# Logic.net
KiCad netlist of a schematic drawn in Altium Designer
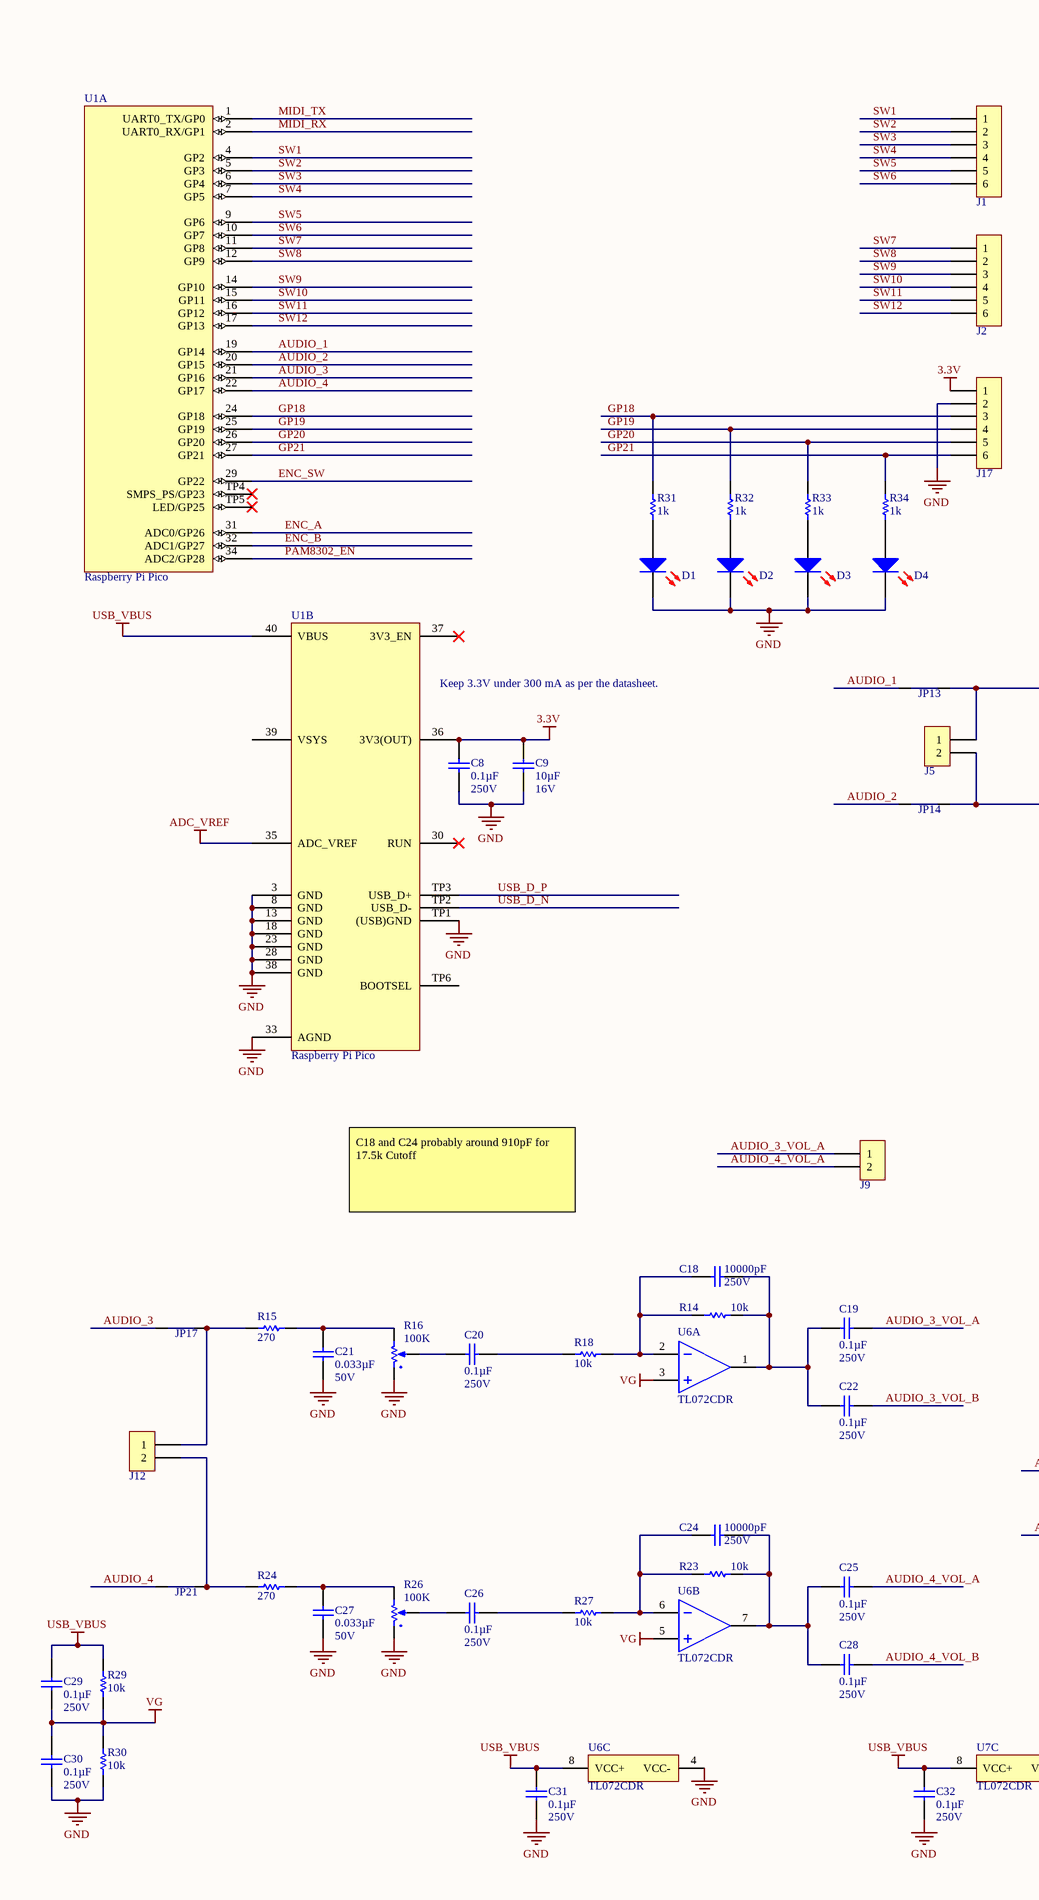
[diagram p0: Logic.SchDoc, left]
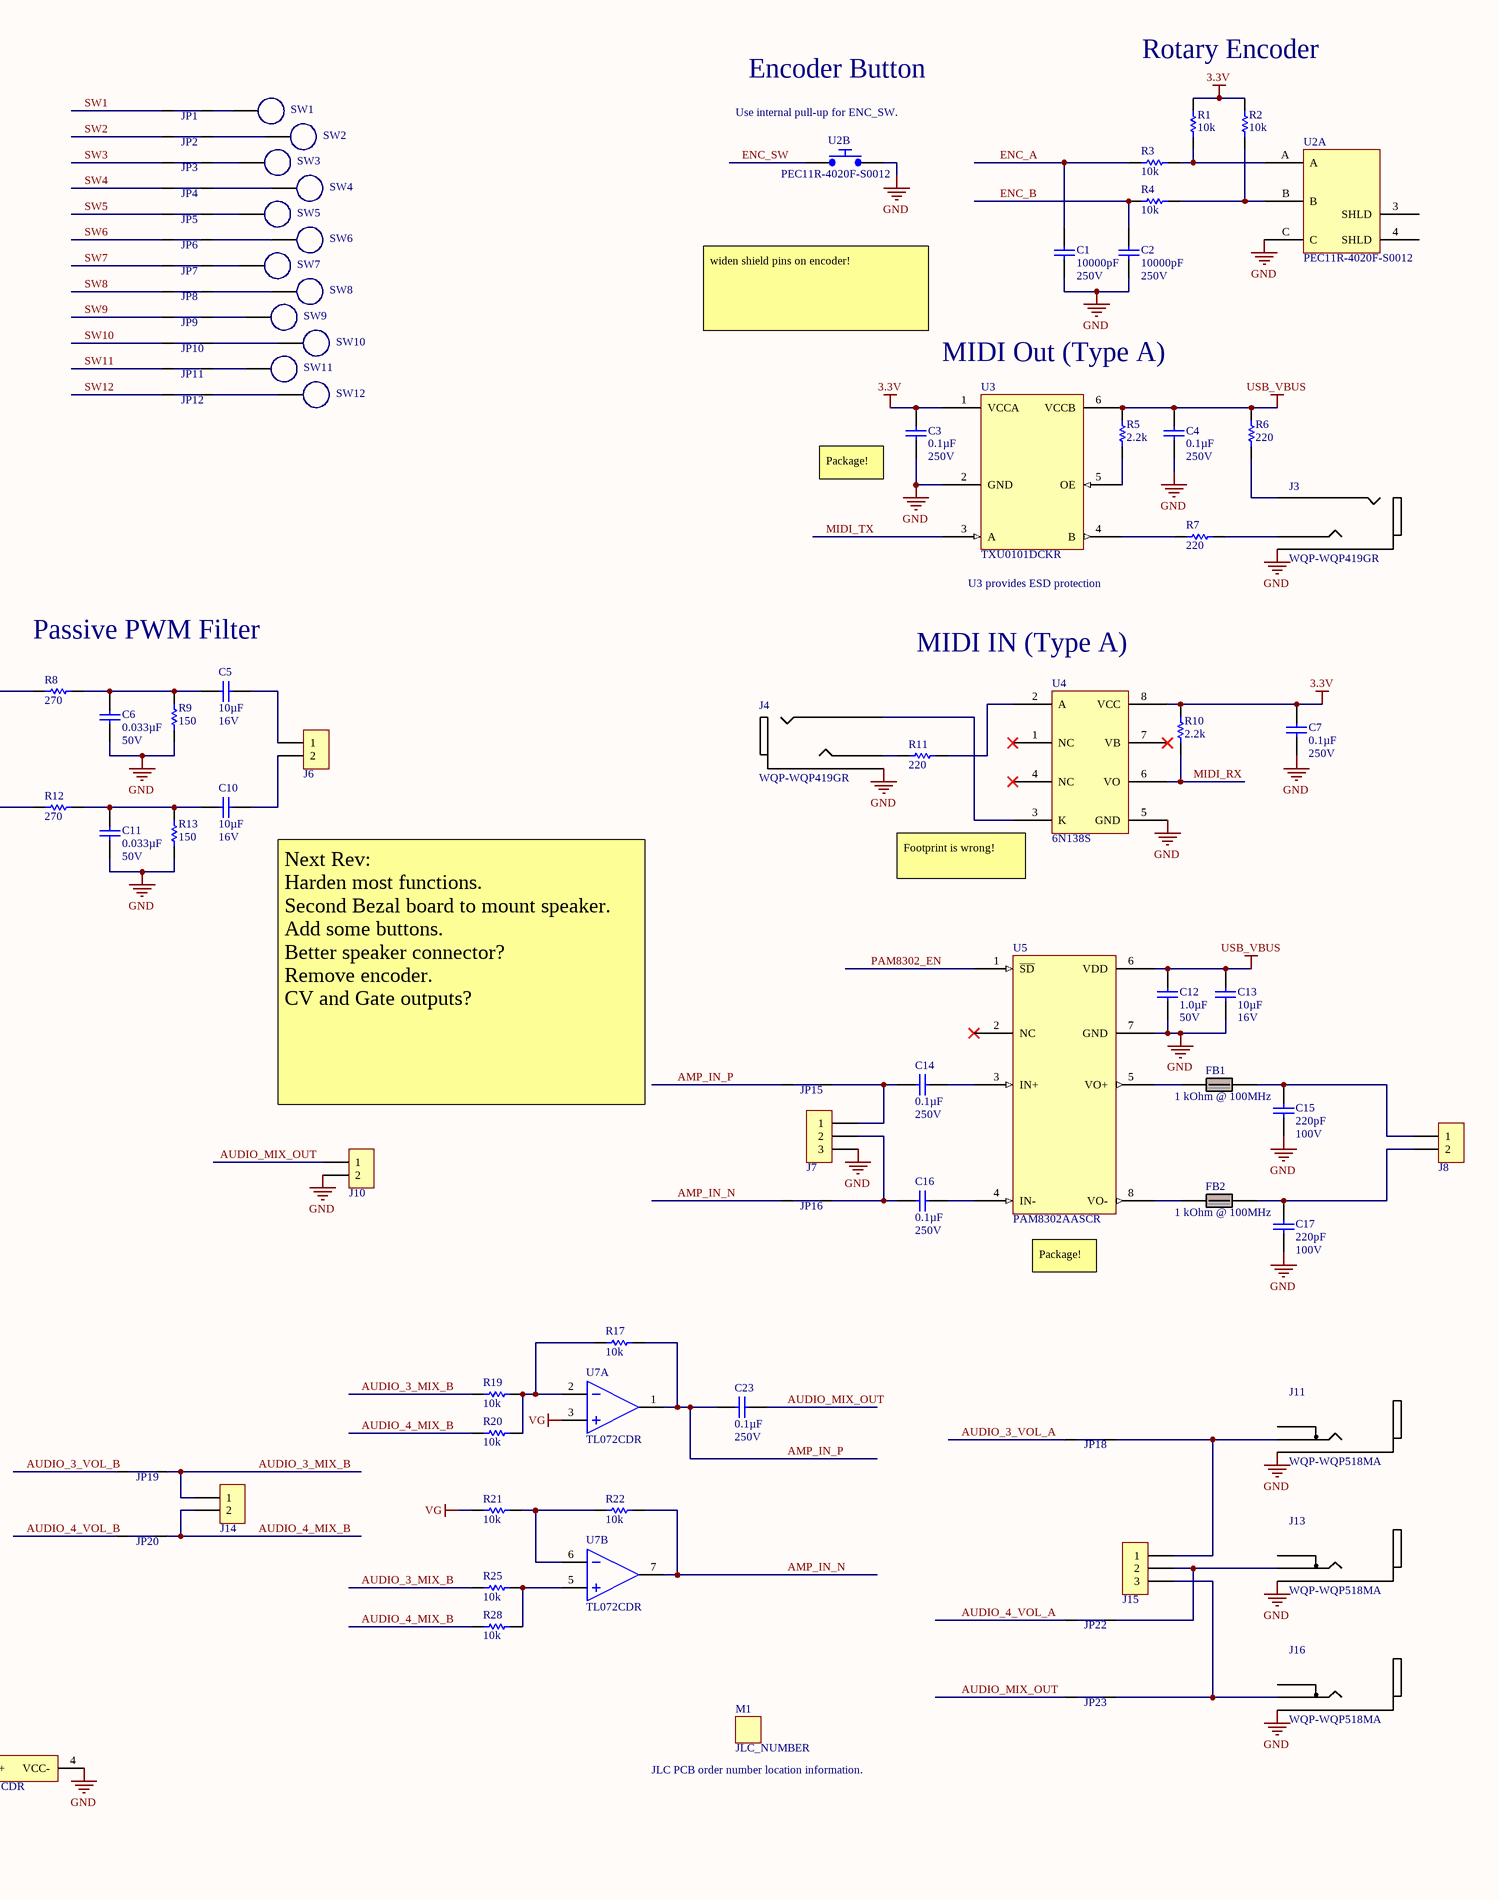
[diagram p1: Logic.SchDoc, right]

(export (version "E")
  (design (tool "Eeschema 10.0.6"))
  (components
    (comp (ref "C1")
      (value "10000pF")
      (footprint "Chip0805")
      (description "CAP CER 10000PF 250V X7R 0805")
      (fields
        (field (name "VOLTAGE") "250V")
        (field (name "PARTNUMBER") "C2012X7R2E103M125AE")
        (field (name "MANUFACTURER") "TDK Corporation")
      )
      (libsource (lib "Passives") (part "CAP"))
    )
    (comp (ref "C2")
      (value "10000pF")
      (footprint "Chip0805")
      (description "CAP CER 10000PF 250V X7R 0805")
      (fields
        (field (name "VOLTAGE") "250V")
        (field (name "PARTNUMBER") "C2012X7R2E103M125AE")
        (field (name "MANUFACTURER") "TDK Corporation")
      )
      (libsource (lib "Passives") (part "CAP"))
    )
    (comp (ref "C3")
      (value "0.1µF")
      (footprint "Chip0805")
      (description "CAP CER 0.1UF 250V 10% X7T 0805")
      (fields
        (field (name "VOLTAGE") "250V")
        (field (name "PARTNUMBER") "C2012X7T2E104K125AA")
        (field (name "MANUFACTURER") "TDK Corporation")
      )
      (libsource (lib "Passives") (part "CAP"))
    )
    (comp (ref "C4")
      (value "0.1µF")
      (footprint "Chip0805")
      (description "CAP CER 0.1UF 250V 10% X7T 0805")
      (fields
        (field (name "VOLTAGE") "250V")
        (field (name "PARTNUMBER") "C2012X7T2E104K125AA")
        (field (name "MANUFACTURER") "TDK Corporation")
      )
      (libsource (lib "Passives") (part "CAP"))
    )
    (comp (ref "C5")
      (value "10µF")
      (footprint "Chip0805")
      (description "CAP CER 10UF 16V 10% X5R 0805")
      (fields
        (field (name "VOLTAGE") "16V")
        (field (name "PARTNUMBER") "C2012X5R1C106K125AC")
        (field (name "MANUFACTURER") "TDK Corporation")
      )
      (libsource (lib "Passives") (part "CAP"))
    )
    (comp (ref "C6")
      (value "0.033µF")
      (footprint "Chip0805")
      (description "CAP CER 0.033UF 50V 5% NP0 0805")
      (fields
        (field (name "VOLTAGE") "50V")
        (field (name "PARTNUMBER") "C2012C0G1H333J125AA")
        (field (name "MANUFACTURER") "TDK Corporation")
      )
      (libsource (lib "Passives") (part "CAP"))
    )
    (comp (ref "C7")
      (value "0.1µF")
      (footprint "Chip0805")
      (description "CAP CER 0.1UF 250V 10% X7T 0805")
      (fields
        (field (name "VOLTAGE") "250V")
        (field (name "PARTNUMBER") "C2012X7T2E104K125AA")
        (field (name "MANUFACTURER") "TDK Corporation")
      )
      (libsource (lib "Passives") (part "CAP"))
    )
    (comp (ref "C8")
      (value "0.1µF")
      (footprint "Chip0805")
      (description "CAP CER 0.1UF 250V 10% X7T 0805")
      (fields
        (field (name "VOLTAGE") "250V")
        (field (name "PARTNUMBER") "C2012X7T2E104K125AA")
        (field (name "MANUFACTURER") "TDK Corporation")
      )
      (libsource (lib "Passives") (part "CAP"))
    )
    (comp (ref "C9")
      (value "10µF")
      (footprint "Chip0805")
      (description "CAP CER 10UF 16V 10% X5R 0805")
      (fields
        (field (name "VOLTAGE") "16V")
        (field (name "PARTNUMBER") "C2012X5R1C106K125AC")
        (field (name "MANUFACTURER") "TDK Corporation")
      )
      (libsource (lib "Passives") (part "CAP"))
    )
    (comp (ref "C10")
      (value "10µF")
      (footprint "Chip0805")
      (description "CAP CER 10UF 16V 10% X5R 0805")
      (fields
        (field (name "VOLTAGE") "16V")
        (field (name "PARTNUMBER") "C2012X5R1C106K125AC")
        (field (name "MANUFACTURER") "TDK Corporation")
      )
      (libsource (lib "Passives") (part "CAP"))
    )
    (comp (ref "C11")
      (value "0.033µF")
      (footprint "Chip0805")
      (description "CAP CER 0.033UF 50V 5% NP0 0805")
      (fields
        (field (name "VOLTAGE") "50V")
        (field (name "PARTNUMBER") "C2012C0G1H333J125AA")
        (field (name "MANUFACTURER") "TDK Corporation")
      )
      (libsource (lib "Passives") (part "CAP"))
    )
    (comp (ref "C12")
      (value "1.0µF")
      (footprint "Chip0805")
      (description "CAP CER 1UF 50V 20% X7R 0805")
      (fields
        (field (name "VOLTAGE") "50V")
        (field (name "PARTNUMBER") "C2012X7R1H105M125AB")
        (field (name "MANUFACTURER") "TDK Corporation")
      )
      (libsource (lib "Passives") (part "CAP"))
    )
    (comp (ref "C13")
      (value "10µF")
      (footprint "Chip0805")
      (description "CAP CER 10UF 16V 10% X5R 0805")
      (fields
        (field (name "VOLTAGE") "16V")
        (field (name "PARTNUMBER") "C2012X5R1C106K125AC")
        (field (name "MANUFACTURER") "TDK Corporation")
      )
      (libsource (lib "Passives") (part "CAP"))
    )
    (comp (ref "C14")
      (value "0.1µF")
      (footprint "Chip0805")
      (description "CAP CER 0.1UF 250V 10% X7T 0805")
      (fields
        (field (name "VOLTAGE") "250V")
        (field (name "PARTNUMBER") "C2012X7T2E104K125AA")
        (field (name "MANUFACTURER") "TDK Corporation")
      )
      (libsource (lib "Passives") (part "CAP"))
    )
    (comp (ref "C15")
      (value "220pF")
      (footprint "Chip0805")
      (description "CAP CER 220PF 100V 5% NP0 0805")
      (fields
        (field (name "VOLTAGE") "100V")
        (field (name "PARTNUMBER") "C2012C0G2A221J")
        (field (name "MANUFACTURER") "TDK Corporation")
      )
      (libsource (lib "Passives") (part "CAP"))
    )
    (comp (ref "C16")
      (value "0.1µF")
      (footprint "Chip0805")
      (description "CAP CER 0.1UF 250V 10% X7T 0805")
      (fields
        (field (name "VOLTAGE") "250V")
        (field (name "PARTNUMBER") "C2012X7T2E104K125AA")
        (field (name "MANUFACTURER") "TDK Corporation")
      )
      (libsource (lib "Passives") (part "CAP"))
    )
    (comp (ref "C17")
      (value "220pF")
      (footprint "Chip0805")
      (description "CAP CER 220PF 100V 5% NP0 0805")
      (fields
        (field (name "VOLTAGE") "100V")
        (field (name "PARTNUMBER") "C2012C0G2A221J")
        (field (name "MANUFACTURER") "TDK Corporation")
      )
      (libsource (lib "Passives") (part "CAP"))
    )
    (comp (ref "C18")
      (value "10000pF")
      (footprint "Chip0805")
      (description "CAP CER 10000PF 250V X7R 0805")
      (fields
        (field (name "VOLTAGE") "250V")
        (field (name "PARTNUMBER") "C2012X7R2E103M125AE")
        (field (name "MANUFACTURER") "TDK Corporation")
      )
      (libsource (lib "Passives") (part "CAP"))
    )
    (comp (ref "C19")
      (value "0.1µF")
      (footprint "Chip0805")
      (description "CAP CER 0.1UF 250V 10% X7T 0805")
      (fields
        (field (name "VOLTAGE") "250V")
        (field (name "PARTNUMBER") "C2012X7T2E104K125AA")
        (field (name "MANUFACTURER") "TDK Corporation")
      )
      (libsource (lib "Passives") (part "CAP"))
    )
    (comp (ref "C20")
      (value "0.1µF")
      (footprint "Chip0805")
      (description "CAP CER 0.1UF 250V 10% X7T 0805")
      (fields
        (field (name "VOLTAGE") "250V")
        (field (name "PARTNUMBER") "C2012X7T2E104K125AA")
        (field (name "MANUFACTURER") "TDK Corporation")
      )
      (libsource (lib "Passives") (part "CAP"))
    )
    (comp (ref "C21")
      (value "0.033µF")
      (footprint "Chip0805")
      (description "CAP CER 0.033UF 50V 5% NP0 0805")
      (fields
        (field (name "VOLTAGE") "50V")
        (field (name "PARTNUMBER") "C2012C0G1H333J125AA")
        (field (name "MANUFACTURER") "TDK Corporation")
      )
      (libsource (lib "Passives") (part "CAP"))
    )
    (comp (ref "C22")
      (value "0.1µF")
      (footprint "Chip0805")
      (description "CAP CER 0.1UF 250V 10% X7T 0805")
      (fields
        (field (name "VOLTAGE") "250V")
        (field (name "PARTNUMBER") "C2012X7T2E104K125AA")
        (field (name "MANUFACTURER") "TDK Corporation")
      )
      (libsource (lib "Passives") (part "CAP"))
    )
    (comp (ref "C23")
      (value "0.1µF")
      (footprint "Chip0805")
      (description "CAP CER 0.1UF 250V 10% X7T 0805")
      (fields
        (field (name "VOLTAGE") "250V")
        (field (name "PARTNUMBER") "C2012X7T2E104K125AA")
        (field (name "MANUFACTURER") "TDK Corporation")
      )
      (libsource (lib "Passives") (part "CAP"))
    )
    (comp (ref "C24")
      (value "10000pF")
      (footprint "Chip0805")
      (description "CAP CER 10000PF 250V X7R 0805")
      (fields
        (field (name "VOLTAGE") "250V")
        (field (name "PARTNUMBER") "C2012X7R2E103M125AE")
        (field (name "MANUFACTURER") "TDK Corporation")
      )
      (libsource (lib "Passives") (part "CAP"))
    )
    (comp (ref "C25")
      (value "0.1µF")
      (footprint "Chip0805")
      (description "CAP CER 0.1UF 250V 10% X7T 0805")
      (fields
        (field (name "VOLTAGE") "250V")
        (field (name "PARTNUMBER") "C2012X7T2E104K125AA")
        (field (name "MANUFACTURER") "TDK Corporation")
      )
      (libsource (lib "Passives") (part "CAP"))
    )
    (comp (ref "C26")
      (value "0.1µF")
      (footprint "Chip0805")
      (description "CAP CER 0.1UF 250V 10% X7T 0805")
      (fields
        (field (name "VOLTAGE") "250V")
        (field (name "PARTNUMBER") "C2012X7T2E104K125AA")
        (field (name "MANUFACTURER") "TDK Corporation")
      )
      (libsource (lib "Passives") (part "CAP"))
    )
    (comp (ref "C27")
      (value "0.033µF")
      (footprint "Chip0805")
      (description "CAP CER 0.033UF 50V 5% NP0 0805")
      (fields
        (field (name "VOLTAGE") "50V")
        (field (name "PARTNUMBER") "C2012C0G1H333J125AA")
        (field (name "MANUFACTURER") "TDK Corporation")
      )
      (libsource (lib "Passives") (part "CAP"))
    )
    (comp (ref "C28")
      (value "0.1µF")
      (footprint "Chip0805")
      (description "CAP CER 0.1UF 250V 10% X7T 0805")
      (fields
        (field (name "VOLTAGE") "250V")
        (field (name "PARTNUMBER") "C2012X7T2E104K125AA")
        (field (name "MANUFACTURER") "TDK Corporation")
      )
      (libsource (lib "Passives") (part "CAP"))
    )
    (comp (ref "C29")
      (value "0.1µF")
      (footprint "Chip0805")
      (description "CAP CER 0.1UF 250V 10% X7T 0805")
      (fields
        (field (name "VOLTAGE") "250V")
        (field (name "PARTNUMBER") "C2012X7T2E104K125AA")
        (field (name "MANUFACTURER") "TDK Corporation")
      )
      (libsource (lib "Passives") (part "CAP"))
    )
    (comp (ref "C30")
      (value "0.1µF")
      (footprint "Chip0805")
      (description "CAP CER 0.1UF 250V 10% X7T 0805")
      (fields
        (field (name "VOLTAGE") "250V")
        (field (name "PARTNUMBER") "C2012X7T2E104K125AA")
        (field (name "MANUFACTURER") "TDK Corporation")
      )
      (libsource (lib "Passives") (part "CAP"))
    )
    (comp (ref "C31")
      (value "0.1µF")
      (footprint "Chip0805")
      (description "CAP CER 0.1UF 250V 10% X7T 0805")
      (fields
        (field (name "VOLTAGE") "250V")
        (field (name "PARTNUMBER") "C2012X7T2E104K125AA")
        (field (name "MANUFACTURER") "TDK Corporation")
      )
      (libsource (lib "Passives") (part "CAP"))
    )
    (comp (ref "C32")
      (value "0.1µF")
      (footprint "Chip0805")
      (description "CAP CER 0.1UF 250V 10% X7T 0805")
      (fields
        (field (name "VOLTAGE") "250V")
        (field (name "PARTNUMBER") "C2012X7T2E104K125AA")
        (field (name "MANUFACTURER") "TDK Corporation")
      )
      (libsource (lib "Passives") (part "CAP"))
    )
    (comp (ref "D1")
      (value "RED")
      (footprint "LED0603")
      (description "LED SUPER RED CLR THIN 0603 SMD")
      (fields (field (name "PARTNUMBER") "LTST-C191KRKT") (field (name "MANUFACTURER") "Lite-On Inc"))
      (libsource (lib "Optoelectronics") (part "LED_RED"))
    )
    (comp (ref "D2")
      (value "RED")
      (footprint "LED0603")
      (description "LED SUPER RED CLR THIN 0603 SMD")
      (fields (field (name "PARTNUMBER") "LTST-C191KRKT") (field (name "MANUFACTURER") "Lite-On Inc"))
      (libsource (lib "Optoelectronics") (part "LED_RED"))
    )
    (comp (ref "D3")
      (value "RED")
      (footprint "LED0603")
      (description "LED SUPER RED CLR THIN 0603 SMD")
      (fields (field (name "PARTNUMBER") "LTST-C191KRKT") (field (name "MANUFACTURER") "Lite-On Inc"))
      (libsource (lib "Optoelectronics") (part "LED_RED"))
    )
    (comp (ref "D4")
      (value "RED")
      (footprint "LED0603")
      (description "LED SUPER RED CLR THIN 0603 SMD")
      (fields (field (name "PARTNUMBER") "LTST-C191KRKT") (field (name "MANUFACTURER") "Lite-On Inc"))
      (libsource (lib "Optoelectronics") (part "LED_RED"))
    )
    (comp (ref "FB1")
      (value "FERRITE")
      (footprint "Chip0805")
      (description "FERRITE BEAD 1000 OHM .20A 0805")
      (fields
        (field (name "IMPEDANCE @ FREQUENCY") "1 kOhm @ 100MHz")
        (field (name "PARTNUMBER") "74279205")
        (field (name "MANUFACTURER") "Wurth Electronics Inc")
      )
      (libsource (lib "Passives") (part "FERRITE"))
    )
    (comp (ref "FB2")
      (value "FERRITE")
      (footprint "Chip0805")
      (description "FERRITE BEAD 1000 OHM .20A 0805")
      (fields
        (field (name "IMPEDANCE @ FREQUENCY") "1 kOhm @ 100MHz")
        (field (name "PARTNUMBER") "74279205")
        (field (name "MANUFACTURER") "Wurth Electronics Inc")
      )
      (libsource (lib "Passives") (part "FERRITE"))
    )
    (comp (ref "J1")
      (value "HEADER_1x6_NO_BOM")
      (footprint "HEADER_1x6_100mil_NP")
      (libsource (lib "Mechanical") (part "HEADER_1x6_NO_BOM"))
    )
    (comp (ref "J2")
      (value "HEADER_1x6_NO_BOM")
      (footprint "HEADER_1x6_100mil_NP")
      (libsource (lib "Mechanical") (part "HEADER_1x6_NO_BOM"))
    )
    (comp (ref "J3")
      (value "WQP-WQP419GR")
      (footprint "PJ366ST")
      (description "CONN 3.5mm VIRTICAL STEREO")
      (fields (field (name "MANUFACTURER") "QingPu"))
      (libsource (lib "Connectors") (part "PJ366ST"))
    )
    (comp (ref "J4")
      (value "WQP-WQP419GR")
      (footprint "PJ366ST")
      (description "CONN 3.5mm VIRTICAL STEREO")
      (fields (field (name "MANUFACTURER") "QingPu"))
      (libsource (lib "Connectors") (part "PJ366ST"))
    )
    (comp (ref "J5")
      (value "HEADER_1x2_NO_BOM")
      (footprint "HEADER_1x2_100mil_NP")
      (libsource (lib "") (part "HEADER_1x2_NO_BOM_1"))
    )
    (comp (ref "J6")
      (value "HEADER_1x2_NO_BOM")
      (footprint "HEADER_1x2_100mil_NP")
      (libsource (lib "Mechanical") (part "HEADER_1x2_NO_BOM"))
    )
    (comp (ref "J7")
      (value "HEADER_1x3_NO_BOM")
      (footprint "HEADER_1x3_100mil_NP")
      (libsource (lib "Mechanical") (part "HEADER_1x3_NO_BOM"))
    )
    (comp (ref "J8")
      (value "HEADER_1x2_NO_BOM")
      (footprint "HEADER_1x2_100mil_NP")
      (libsource (lib "Mechanical") (part "HEADER_1x2_NO_BOM"))
    )
    (comp (ref "J9")
      (value "HEADER_1x2_NO_BOM")
      (footprint "HEADER_1x2_100mil_NP")
      (libsource (lib "Mechanical") (part "HEADER_1x2_NO_BOM"))
    )
    (comp (ref "J10")
      (value "HEADER_1x2_NO_BOM")
      (footprint "HEADER_1x2_100mil_NP")
      (libsource (lib "Mechanical") (part "HEADER_1x2_NO_BOM"))
    )
    (comp (ref "J11")
      (value "WQP-WQP518MA")
      (footprint "PJ301M-12")
      (description "CONN 3.5mm VIRTICAL MONO w/ NORMAL")
      (fields (field (name "MANUFACTURER") "QingPu"))
      (libsource (lib "Connectors") (part "PJ301M-12"))
    )
    (comp (ref "J12")
      (value "HEADER_1x2_NO_BOM")
      (footprint "HEADER_1x2_100mil_NP")
      (libsource (lib "") (part "HEADER_1x2_NO_BOM_1"))
    )
    (comp (ref "J13")
      (value "WQP-WQP518MA")
      (footprint "PJ301M-12")
      (description "CONN 3.5mm VIRTICAL MONO w/ NORMAL")
      (fields (field (name "MANUFACTURER") "QingPu"))
      (libsource (lib "Connectors") (part "PJ301M-12"))
    )
    (comp (ref "J14")
      (value "HEADER_1x2_NO_BOM")
      (footprint "HEADER_1x2_100mil_NP")
      (libsource (lib "Mechanical") (part "HEADER_1x2_NO_BOM"))
    )
    (comp (ref "J15")
      (value "HEADER_1x3_NO_BOM")
      (footprint "HEADER_1x3_100mil_NP")
      (libsource (lib "Mechanical") (part "HEADER_1x3_NO_BOM"))
    )
    (comp (ref "J16")
      (value "WQP-WQP518MA")
      (footprint "PJ301M-12")
      (description "CONN 3.5mm VIRTICAL MONO w/ NORMAL")
      (fields (field (name "MANUFACTURER") "QingPu"))
      (libsource (lib "Connectors") (part "PJ301M-12"))
    )
    (comp (ref "J17")
      (value "HEADER_1x6_NO_BOM")
      (footprint "HEADER_1x6_100mil_NP")
      (libsource (lib "Mechanical") (part "HEADER_1x6_NO_BOM"))
    )
    (comp (ref "JP1")
      (value "JUMMPER_NC_0805")
      (footprint "JUMMPER_NC_0805")
      (libsource (lib "Mechanical") (part "JUMPER_NC"))
    )
    (comp (ref "JP2")
      (value "JUMMPER_NC_0805")
      (footprint "JUMMPER_NC_0805")
      (libsource (lib "Mechanical") (part "JUMPER_NC"))
    )
    (comp (ref "JP3")
      (value "JUMMPER_NC_0805")
      (footprint "JUMMPER_NC_0805")
      (libsource (lib "Mechanical") (part "JUMPER_NC"))
    )
    (comp (ref "JP4")
      (value "JUMMPER_NC_0805")
      (footprint "JUMMPER_NC_0805")
      (libsource (lib "Mechanical") (part "JUMPER_NC"))
    )
    (comp (ref "JP5")
      (value "JUMMPER_NC_0805")
      (footprint "JUMMPER_NC_0805")
      (libsource (lib "Mechanical") (part "JUMPER_NC"))
    )
    (comp (ref "JP6")
      (value "JUMMPER_NC_0805")
      (footprint "JUMMPER_NC_0805")
      (libsource (lib "Mechanical") (part "JUMPER_NC"))
    )
    (comp (ref "JP7")
      (value "JUMMPER_NC_0805")
      (footprint "JUMMPER_NC_0805")
      (libsource (lib "Mechanical") (part "JUMPER_NC"))
    )
    (comp (ref "JP8")
      (value "JUMMPER_NC_0805")
      (footprint "JUMMPER_NC_0805")
      (libsource (lib "Mechanical") (part "JUMPER_NC"))
    )
    (comp (ref "JP9")
      (value "JUMMPER_NC_0805")
      (footprint "JUMMPER_NC_0805")
      (libsource (lib "Mechanical") (part "JUMPER_NC"))
    )
    (comp (ref "JP10")
      (value "JUMMPER_NC_0805")
      (footprint "JUMMPER_NC_0805")
      (libsource (lib "Mechanical") (part "JUMPER_NC"))
    )
    (comp (ref "JP11")
      (value "JUMMPER_NC_0805")
      (footprint "JUMMPER_NC_0805")
      (libsource (lib "Mechanical") (part "JUMPER_NC"))
    )
    (comp (ref "JP12")
      (value "JUMMPER_NC_0805")
      (footprint "JUMMPER_NC_0805")
      (libsource (lib "Mechanical") (part "JUMPER_NC"))
    )
    (comp (ref "JP13")
      (value "JUMMPER_NC_0805")
      (footprint "JUMMPER_NC_0805")
      (libsource (lib "Mechanical") (part "JUMPER_NC"))
    )
    (comp (ref "JP14")
      (value "JUMMPER_NC_0805")
      (footprint "JUMMPER_NC_0805")
      (libsource (lib "Mechanical") (part "JUMPER_NC"))
    )
    (comp (ref "JP15")
      (value "JUMMPER_NC_0805")
      (footprint "JUMMPER_NC_0805")
      (libsource (lib "Mechanical") (part "JUMPER_NC"))
    )
    (comp (ref "JP16")
      (value "JUMMPER_NC_0805")
      (footprint "JUMMPER_NC_0805")
      (libsource (lib "Mechanical") (part "JUMPER_NC"))
    )
    (comp (ref "JP17")
      (value "JUMMPER_NC_0805")
      (footprint "JUMMPER_NC_0805")
      (libsource (lib "Mechanical") (part "JUMPER_NC"))
    )
    (comp (ref "JP18")
      (value "JUMMPER_NC_0805")
      (footprint "JUMMPER_NC_0805")
      (libsource (lib "Mechanical") (part "JUMPER_NC"))
    )
    (comp (ref "JP19")
      (value "JUMMPER_NC_0805")
      (footprint "JUMMPER_NC_0805")
      (libsource (lib "Mechanical") (part "JUMPER_NC"))
    )
    (comp (ref "JP20")
      (value "JUMMPER_NC_0805")
      (footprint "JUMMPER_NC_0805")
      (libsource (lib "Mechanical") (part "JUMPER_NC"))
    )
    (comp (ref "JP21")
      (value "JUMMPER_NC_0805")
      (footprint "JUMMPER_NC_0805")
      (libsource (lib "Mechanical") (part "JUMPER_NC"))
    )
    (comp (ref "JP22")
      (value "JUMMPER_NC_0805")
      (footprint "JUMMPER_NC_0805")
      (libsource (lib "Mechanical") (part "JUMPER_NC"))
    )
    (comp (ref "JP23")
      (value "JUMMPER_NC_0805")
      (footprint "JUMMPER_NC_0805")
      (libsource (lib "Mechanical") (part "JUMPER_NC"))
    )
    (comp (ref "M1")
      (value "JLC_NUMBER")
      (footprint "JLC_NUMBER")
      (description "JLC Order Number Location")
      (libsource (lib "Mechanical") (part "MECH_NO_BOM"))
    )
    (comp (ref "R1")
      (value "10k")
      (footprint "Chip0805")
      (description "RES 10.0K OHM 1/8W 1% 0805 SMD")
      (fields (field (name "PARTNUMBER") "CRCW080510K0FKEA") (field (name "MANUFACTURER") "Vishay Dale"))
      (libsource (lib "Passives") (part "RES"))
    )
    (comp (ref "R2")
      (value "10k")
      (footprint "Chip0805")
      (description "RES 10.0K OHM 1/8W 1% 0805 SMD")
      (fields (field (name "PARTNUMBER") "CRCW080510K0FKEA") (field (name "MANUFACTURER") "Vishay Dale"))
      (libsource (lib "Passives") (part "RES"))
    )
    (comp (ref "R3")
      (value "10k")
      (footprint "Chip0805")
      (description "RES 10.0K OHM 1/8W 1% 0805 SMD")
      (fields (field (name "PARTNUMBER") "CRCW080510K0FKEA") (field (name "MANUFACTURER") "Vishay Dale"))
      (libsource (lib "Passives") (part "RES"))
    )
    (comp (ref "R4")
      (value "10k")
      (footprint "Chip0805")
      (description "RES 10.0K OHM 1/8W 1% 0805 SMD")
      (fields (field (name "PARTNUMBER") "CRCW080510K0FKEA") (field (name "MANUFACTURER") "Vishay Dale"))
      (libsource (lib "Passives") (part "RES"))
    )
    (comp (ref "R5")
      (value "2.2k")
      (footprint "Chip0805")
      (description "RES 2.20K OHM 1/8W 1% 0805 SMD")
      (fields (field (name "PARTNUMBER") "CRCW08052K20FKEA") (field (name "MANUFACTURER") "Vishay Dale"))
      (libsource (lib "Passives") (part "RES"))
    )
    (comp (ref "R6")
      (value "220")
      (footprint "Chip0805")
      (description "RES 220 OHM 1/8W 1% 0805 SMD")
      (fields (field (name "PARTNUMBER") "CRCW0805220RFKEA") (field (name "MANUFACTURER") "Vishay Dale"))
      (libsource (lib "Passives") (part "RES"))
    )
    (comp (ref "R7")
      (value "220")
      (footprint "Chip0805")
      (description "RES 220 OHM 1/8W 1% 0805 SMD")
      (fields (field (name "PARTNUMBER") "CRCW0805220RFKEA") (field (name "MANUFACTURER") "Vishay Dale"))
      (libsource (lib "Passives") (part "RES"))
    )
    (comp (ref "R8")
      (value "270")
      (footprint "Chip0805")
      (description "RES 270 OHM 1/8W 1% 0805 SMD")
      (fields (field (name "PARTNUMBER") "CRCW0805270RFKEA") (field (name "MANUFACTURER") "Vishay Dale"))
      (libsource (lib "Passives") (part "RES"))
    )
    (comp (ref "R9")
      (value "150")
      (footprint "Chip0805")
      (description "RES 150 OHM 1/8W 1% 0805 SMD")
      (fields (field (name "PARTNUMBER") "CRCW0805150RFKEA") (field (name "MANUFACTURER") "Vishay Dale"))
      (libsource (lib "Passives") (part "RES"))
    )
    (comp (ref "R10")
      (value "2.2k")
      (footprint "Chip0805")
      (description "RES 2.20K OHM 1/8W 1% 0805 SMD")
      (fields (field (name "PARTNUMBER") "CRCW08052K20FKEA") (field (name "MANUFACTURER") "Vishay Dale"))
      (libsource (lib "Passives") (part "RES"))
    )
    (comp (ref "R11")
      (value "220")
      (footprint "Chip0805")
      (description "RES 220 OHM 1/8W 1% 0805 SMD")
      (fields (field (name "PARTNUMBER") "CRCW0805220RFKEA") (field (name "MANUFACTURER") "Vishay Dale"))
      (libsource (lib "Passives") (part "RES"))
    )
    (comp (ref "R12")
      (value "270")
      (footprint "Chip0805")
      (description "RES 270 OHM 1/8W 1% 0805 SMD")
      (fields (field (name "PARTNUMBER") "CRCW0805270RFKEA") (field (name "MANUFACTURER") "Vishay Dale"))
      (libsource (lib "Passives") (part "RES"))
    )
    (comp (ref "R13")
      (value "150")
      (footprint "Chip0805")
      (description "RES 150 OHM 1/8W 1% 0805 SMD")
      (fields (field (name "PARTNUMBER") "CRCW0805150RFKEA") (field (name "MANUFACTURER") "Vishay Dale"))
      (libsource (lib "Passives") (part "RES"))
    )
    (comp (ref "R14")
      (value "10k")
      (footprint "Chip0805")
      (description "RES 10.0K OHM 1/8W 1% 0805 SMD")
      (fields (field (name "PARTNUMBER") "CRCW080510K0FKEA") (field (name "MANUFACTURER") "Vishay Dale"))
      (libsource (lib "Passives") (part "RES"))
    )
    (comp (ref "R15")
      (value "270")
      (footprint "Chip0805")
      (description "RES 270 OHM 1/8W 1% 0805 SMD")
      (fields (field (name "PARTNUMBER") "CRCW0805270RFKEA") (field (name "MANUFACTURER") "Vishay Dale"))
      (libsource (lib "Passives") (part "RES"))
    )
    (comp (ref "R16")
      (value "100K")
      (footprint "Alpha_RD901F-40-15R")
      (description "POT 100K OHM 9MM RD 1/20W")
      (fields
        (field (name "PARTNUMBER") "RD901F-40-15R-B100K")
        (field (name "MANUFACTURER") "Alpha (Taiwan)")
      )
      (libsource (lib "Passives") (part "POT"))
    )
    (comp (ref "R17")
      (value "10k")
      (footprint "Chip0805")
      (description "RES 10.0K OHM 1/8W 1% 0805 SMD")
      (fields (field (name "PARTNUMBER") "CRCW080510K0FKEA") (field (name "MANUFACTURER") "Vishay Dale"))
      (libsource (lib "Passives") (part "RES"))
    )
    (comp (ref "R18")
      (value "10k")
      (footprint "Chip0805")
      (description "RES 10.0K OHM 1/8W 1% 0805 SMD")
      (fields (field (name "PARTNUMBER") "CRCW080510K0FKEA") (field (name "MANUFACTURER") "Vishay Dale"))
      (libsource (lib "Passives") (part "RES"))
    )
    (comp (ref "R19")
      (value "10k")
      (footprint "Chip0805")
      (description "RES 10.0K OHM 1/8W 1% 0805 SMD")
      (fields (field (name "PARTNUMBER") "CRCW080510K0FKEA") (field (name "MANUFACTURER") "Vishay Dale"))
      (libsource (lib "Passives") (part "RES"))
    )
    (comp (ref "R20")
      (value "10k")
      (footprint "Chip0805")
      (description "RES 10.0K OHM 1/8W 1% 0805 SMD")
      (fields (field (name "PARTNUMBER") "CRCW080510K0FKEA") (field (name "MANUFACTURER") "Vishay Dale"))
      (libsource (lib "Passives") (part "RES"))
    )
    (comp (ref "R21")
      (value "10k")
      (footprint "Chip0805")
      (description "RES 10.0K OHM 1/8W 1% 0805 SMD")
      (fields (field (name "PARTNUMBER") "CRCW080510K0FKEA") (field (name "MANUFACTURER") "Vishay Dale"))
      (libsource (lib "Passives") (part "RES"))
    )
    (comp (ref "R22")
      (value "10k")
      (footprint "Chip0805")
      (description "RES 10.0K OHM 1/8W 1% 0805 SMD")
      (fields (field (name "PARTNUMBER") "CRCW080510K0FKEA") (field (name "MANUFACTURER") "Vishay Dale"))
      (libsource (lib "Passives") (part "RES"))
    )
    (comp (ref "R23")
      (value "10k")
      (footprint "Chip0805")
      (description "RES 10.0K OHM 1/8W 1% 0805 SMD")
      (fields (field (name "PARTNUMBER") "CRCW080510K0FKEA") (field (name "MANUFACTURER") "Vishay Dale"))
      (libsource (lib "Passives") (part "RES"))
    )
    (comp (ref "R24")
      (value "270")
      (footprint "Chip0805")
      (description "RES 270 OHM 1/8W 1% 0805 SMD")
      (fields (field (name "PARTNUMBER") "CRCW0805270RFKEA") (field (name "MANUFACTURER") "Vishay Dale"))
      (libsource (lib "Passives") (part "RES"))
    )
    (comp (ref "R25")
      (value "10k")
      (footprint "Chip0805")
      (description "RES 10.0K OHM 1/8W 1% 0805 SMD")
      (fields (field (name "PARTNUMBER") "CRCW080510K0FKEA") (field (name "MANUFACTURER") "Vishay Dale"))
      (libsource (lib "Passives") (part "RES"))
    )
    (comp (ref "R26")
      (value "100K")
      (footprint "Alpha_RD901F-40-15R")
      (description "POT 100K OHM 9MM RD 1/20W")
      (fields
        (field (name "PARTNUMBER") "RD901F-40-15R-B100K")
        (field (name "MANUFACTURER") "Alpha (Taiwan)")
      )
      (libsource (lib "Passives") (part "POT"))
    )
    (comp (ref "R27")
      (value "10k")
      (footprint "Chip0805")
      (description "RES 10.0K OHM 1/8W 1% 0805 SMD")
      (fields (field (name "PARTNUMBER") "CRCW080510K0FKEA") (field (name "MANUFACTURER") "Vishay Dale"))
      (libsource (lib "Passives") (part "RES"))
    )
    (comp (ref "R28")
      (value "10k")
      (footprint "Chip0805")
      (description "RES 10.0K OHM 1/8W 1% 0805 SMD")
      (fields (field (name "PARTNUMBER") "CRCW080510K0FKEA") (field (name "MANUFACTURER") "Vishay Dale"))
      (libsource (lib "Passives") (part "RES"))
    )
    (comp (ref "R29")
      (value "10k")
      (footprint "Chip0805")
      (description "RES 10.0K OHM 1/8W 1% 0805 SMD")
      (fields (field (name "PARTNUMBER") "CRCW080510K0FKEA") (field (name "MANUFACTURER") "Vishay Dale"))
      (libsource (lib "Passives") (part "RES"))
    )
    (comp (ref "R30")
      (value "10k")
      (footprint "Chip0805")
      (description "RES 10.0K OHM 1/8W 1% 0805 SMD")
      (fields (field (name "PARTNUMBER") "CRCW080510K0FKEA") (field (name "MANUFACTURER") "Vishay Dale"))
      (libsource (lib "Passives") (part "RES"))
    )
    (comp (ref "R31")
      (value "1k")
      (footprint "Chip0805")
      (description "RES 1.00K OHM 1/8W 1% 0805 SMD")
      (fields (field (name "PARTNUMBER") "CRCW08051K00FKEA") (field (name "MANUFACTURER") "Vishay Dale"))
      (libsource (lib "Passives") (part "RES"))
    )
    (comp (ref "R32")
      (value "1k")
      (footprint "Chip0805")
      (description "RES 1.00K OHM 1/8W 1% 0805 SMD")
      (fields (field (name "PARTNUMBER") "CRCW08051K00FKEA") (field (name "MANUFACTURER") "Vishay Dale"))
      (libsource (lib "Passives") (part "RES"))
    )
    (comp (ref "R33")
      (value "1k")
      (footprint "Chip0805")
      (description "RES 1.00K OHM 1/8W 1% 0805 SMD")
      (fields (field (name "PARTNUMBER") "CRCW08051K00FKEA") (field (name "MANUFACTURER") "Vishay Dale"))
      (libsource (lib "Passives") (part "RES"))
    )
    (comp (ref "R34")
      (value "1k")
      (footprint "Chip0805")
      (description "RES 1.00K OHM 1/8W 1% 0805 SMD")
      (fields (field (name "PARTNUMBER") "CRCW08051K00FKEA") (field (name "MANUFACTURER") "Vishay Dale"))
      (libsource (lib "Passives") (part "RES"))
    )
    (comp (ref "SW1")
      (value "TOUCH_PAD_NO_BOM")
      (footprint "TENTED_PAD_5mil")
      (libsource (lib "Mechanical") (part "TOUCH_PAD_NO_BOM"))
    )
    (comp (ref "SW2")
      (value "TOUCH_PAD_NO_BOM")
      (footprint "TENTED_PAD_5mil")
      (libsource (lib "Mechanical") (part "TOUCH_PAD_NO_BOM"))
    )
    (comp (ref "SW3")
      (value "TOUCH_PAD_NO_BOM")
      (footprint "TENTED_PAD_5mil")
      (libsource (lib "Mechanical") (part "TOUCH_PAD_NO_BOM"))
    )
    (comp (ref "SW4")
      (value "TOUCH_PAD_NO_BOM")
      (footprint "TENTED_PAD_5mil")
      (libsource (lib "Mechanical") (part "TOUCH_PAD_NO_BOM"))
    )
    (comp (ref "SW5")
      (value "TOUCH_PAD_NO_BOM")
      (footprint "TENTED_PAD_5mil")
      (libsource (lib "Mechanical") (part "TOUCH_PAD_NO_BOM"))
    )
    (comp (ref "SW6")
      (value "TOUCH_PAD_NO_BOM")
      (footprint "TENTED_PAD_5mil")
      (libsource (lib "Mechanical") (part "TOUCH_PAD_NO_BOM"))
    )
    (comp (ref "SW7")
      (value "TOUCH_PAD_NO_BOM")
      (footprint "TENTED_PAD_5mil")
      (libsource (lib "Mechanical") (part "TOUCH_PAD_NO_BOM"))
    )
    (comp (ref "SW8")
      (value "TOUCH_PAD_NO_BOM")
      (footprint "TENTED_PAD_5mil")
      (libsource (lib "Mechanical") (part "TOUCH_PAD_NO_BOM"))
    )
    (comp (ref "SW9")
      (value "TOUCH_PAD_NO_BOM")
      (footprint "TENTED_PAD_5mil")
      (libsource (lib "Mechanical") (part "TOUCH_PAD_NO_BOM"))
    )
    (comp (ref "SW10")
      (value "TOUCH_PAD_NO_BOM")
      (footprint "TENTED_PAD_5mil")
      (libsource (lib "Mechanical") (part "TOUCH_PAD_NO_BOM"))
    )
    (comp (ref "SW11")
      (value "TOUCH_PAD_NO_BOM")
      (footprint "TENTED_PAD_5mil")
      (libsource (lib "Mechanical") (part "TOUCH_PAD_NO_BOM"))
    )
    (comp (ref "SW12")
      (value "TOUCH_PAD_NO_BOM")
      (footprint "TENTED_PAD_5mil")
      (libsource (lib "Mechanical") (part "TOUCH_PAD_NO_BOM"))
    )
    (comp (ref "U1")
      (value "Raspberry Pi Pico")
      (footprint "RASPBERRY_PI_PICO")
      (description "RASPBERRY PI PICO RP2040 BOARD")
      (fields (field (name "MANUFACTURER PART NUMBER") "SC0915") (field (name "MANUFACTURER") "Raspberry Pi"))
      (libsource (lib "ICs") (part "PI_PICO_SC0915"))
    )
    (comp (ref "U2")
      (value "PEC11R-4020F-S0012")
      (footprint "BOURNS_PEC11R-4020F-S")
      (description "ROTARY ENCODER MECHANICAL 12PPR")
      (fields (field (name "MANUFACTURER") "Bourns Inc."))
      (libsource (lib "") (part "ROTARY_ENCODER_SWITCH_1"))
    )
    (comp (ref "U3")
      (value "TXU0101DCKR")
      (footprint "6-TSSOP")
      (description "SINGLE CHANNEL FIXED-DIRECTION L")
      (fields (field (name "MANUFACTURER") "Texas Instruments"))
      (libsource (lib "ICs") (part "TI_TXU0101"))
    )
    (comp (ref "U4")
      (value "6N138S")
      (footprint "6N13XS")
      (description "OPTOISO 5KV DARL W/BASE 8SMD")
      (fields (field (name "MANUFACTURER") "Lite-On Inc."))
      (libsource (lib "ICs") (part "6N13X"))
    )
    (comp (ref "U5")
      (value "PAM8302AASCR")
      (footprint "8-MSOP")
      (description "IC AMP CLASS D MONO 2.5W 8MSOP")
      (fields (field (name "MANUFACTURER") "Diodes Incorporated"))
      (libsource (lib "ICs") (part "PAM8302A"))
    )
    (comp (ref "U6")
      (value "TL072CDR")
      (footprint "8-SOIC")
      (description "IC OPAMP JFET 3MHZ 8SOIC")
      (fields (field (name "MANUFACTURER") "Texas Instruments"))
      (libsource (lib "ICs") (part "Dual_Op_Amp"))
    )
    (comp (ref "U7")
      (value "TL072CDR")
      (footprint "8-SOIC")
      (description "IC OPAMP JFET 3MHZ 8SOIC")
      (fields (field (name "MANUFACTURER") "Texas Instruments"))
      (libsource (lib "ICs") (part "Dual_Op_Amp"))
    )
  )
  (nets
    (net (code "1") (name "/AMP_IN_N") (class "Default")
      (node (ref "JP16") (pin "1") (pinfunction "1_1") (pintype "passive"))
      (node (ref "R22") (pin "1") (pinfunction "1_1") (pintype "passive"))
      (node (ref "U7") (pin "7") (pinfunction "OUT2_7") (pintype "passive"))
    )
    (net (code "2") (name "/AMP_IN_P") (class "Default")
      (node (ref "C23") (pin "2") (pinfunction "2_2") (pintype "passive"))
      (node (ref "JP15") (pin "1") (pinfunction "1_1") (pintype "passive"))
      (node (ref "R17") (pin "1") (pinfunction "1_1") (pintype "passive"))
      (node (ref "U7") (pin "1") (pinfunction "OUT1_1") (pintype "passive"))
    )
    (net (code "3") (name "/AUDIO_1") (class "Default")
      (node (ref "JP13") (pin "1") (pinfunction "1_1") (pintype "passive"))
      (node (ref "U1") (pin "19") (pinfunction "GP14_19") (pintype "bidirectional"))
    )
    (net (code "4") (name "/AUDIO_2") (class "Default")
      (node (ref "JP14") (pin "1") (pinfunction "1_1") (pintype "passive"))
      (node (ref "U1") (pin "20") (pinfunction "GP15_20") (pintype "bidirectional"))
    )
    (net (code "5") (name "/AUDIO_3") (class "Default")
      (node (ref "JP17") (pin "1") (pinfunction "1_1") (pintype "passive"))
      (node (ref "U1") (pin "21") (pinfunction "GP16_21") (pintype "bidirectional"))
    )
    (net (code "6") (name "/AUDIO_3_MIX_B") (class "Default")
      (node (ref "J14") (pin "1") (pinfunction "1_1") (pintype "passive"))
      (node (ref "JP19") (pin "2") (pinfunction "2_2") (pintype "passive"))
      (node (ref "R19") (pin "2") (pinfunction "2_2") (pintype "passive"))
      (node (ref "R25") (pin "2") (pinfunction "2_2") (pintype "passive"))
    )
    (net (code "7") (name "/AUDIO_3_VOL_A") (class "Default")
      (node (ref "C19") (pin "1") (pinfunction "1_1") (pintype "passive"))
      (node (ref "J9") (pin "1") (pinfunction "1_1") (pintype "passive"))
      (node (ref "JP18") (pin "1") (pinfunction "1_1") (pintype "passive"))
    )
    (net (code "8") (name "/AUDIO_3_VOL_B") (class "Default")
      (node (ref "C22") (pin "1") (pinfunction "1_1") (pintype "passive"))
      (node (ref "JP19") (pin "1") (pinfunction "1_1") (pintype "passive"))
    )
    (net (code "9") (name "/AUDIO_4") (class "Default")
      (node (ref "JP21") (pin "1") (pinfunction "1_1") (pintype "passive"))
      (node (ref "U1") (pin "22") (pinfunction "GP17_22") (pintype "bidirectional"))
    )
    (net (code "10") (name "/AUDIO_4_MIX_B") (class "Default")
      (node (ref "J14") (pin "2") (pinfunction "2_2") (pintype "passive"))
      (node (ref "JP20") (pin "2") (pinfunction "2_2") (pintype "passive"))
      (node (ref "R20") (pin "2") (pinfunction "2_2") (pintype "passive"))
      (node (ref "R28") (pin "2") (pinfunction "2_2") (pintype "passive"))
    )
    (net (code "11") (name "/AUDIO_4_VOL_A") (class "Default")
      (node (ref "C25") (pin "1") (pinfunction "1_1") (pintype "passive"))
      (node (ref "J9") (pin "2") (pinfunction "2_2") (pintype "passive"))
      (node (ref "JP22") (pin "1") (pinfunction "1_1") (pintype "passive"))
    )
    (net (code "12") (name "/AUDIO_4_VOL_B") (class "Default")
      (node (ref "C28") (pin "1") (pinfunction "1_1") (pintype "passive"))
      (node (ref "JP20") (pin "1") (pinfunction "1_1") (pintype "passive"))
    )
    (net (code "13") (name "/AUDIO_MIX_OUT") (class "Default")
      (node (ref "C23") (pin "1") (pinfunction "1_1") (pintype "passive"))
      (node (ref "J10") (pin "1") (pinfunction "1_1") (pintype "passive"))
      (node (ref "JP23") (pin "1") (pinfunction "1_1") (pintype "passive"))
    )
    (net (code "14") (name "/ENC_A") (class "Default")
      (node (ref "C1") (pin "2") (pinfunction "2_2") (pintype "passive"))
      (node (ref "R3") (pin "2") (pinfunction "2_2") (pintype "passive"))
      (node (ref "U1") (pin "31") (pinfunction "ADC0/GP26_31") (pintype "bidirectional"))
    )
    (net (code "15") (name "/ENC_B") (class "Default")
      (node (ref "C2") (pin "2") (pinfunction "2_2") (pintype "passive"))
      (node (ref "R4") (pin "2") (pinfunction "2_2") (pintype "passive"))
      (node (ref "U1") (pin "32") (pinfunction "ADC1/GP27_32") (pintype "bidirectional"))
    )
    (net (code "16") (name "/ENC_SW") (class "Default")
      (node (ref "U1") (pin "29") (pinfunction "GP22_29") (pintype "bidirectional"))
      (node (ref "U2") (pin "2") (pinfunction "2_2") (pintype "passive"))
    )
    (net (code "17") (name "/GP18") (class "Default")
      (node (ref "J17") (pin "3") (pinfunction "3_3") (pintype "passive"))
      (node (ref "R31") (pin "2") (pinfunction "2_2") (pintype "passive"))
      (node (ref "U1") (pin "24") (pinfunction "GP18_24") (pintype "bidirectional"))
    )
    (net (code "18") (name "/GP19") (class "Default")
      (node (ref "J17") (pin "4") (pinfunction "4_4") (pintype "passive"))
      (node (ref "R32") (pin "2") (pinfunction "2_2") (pintype "passive"))
      (node (ref "U1") (pin "25") (pinfunction "GP19_25") (pintype "bidirectional"))
    )
    (net (code "19") (name "/GP20") (class "Default")
      (node (ref "J17") (pin "5") (pinfunction "5_5") (pintype "passive"))
      (node (ref "R33") (pin "2") (pinfunction "2_2") (pintype "passive"))
      (node (ref "U1") (pin "26") (pinfunction "GP20_26") (pintype "bidirectional"))
    )
    (net (code "20") (name "/GP21") (class "Default")
      (node (ref "J17") (pin "6") (pinfunction "6_6") (pintype "passive"))
      (node (ref "R34") (pin "2") (pinfunction "2_2") (pintype "passive"))
      (node (ref "U1") (pin "27") (pinfunction "GP21_27") (pintype "bidirectional"))
    )
    (net (code "21") (name "/MIDI_RX") (class "Default")
      (node (ref "R10") (pin "1") (pinfunction "1_1") (pintype "passive"))
      (node (ref "U1") (pin "2") (pinfunction "UART0_RX/GP1_2") (pintype "bidirectional"))
      (node (ref "U4") (pin "6") (pinfunction "VO_6") (pintype "passive"))
    )
    (net (code "22") (name "/MIDI_TX") (class "Default")
      (node (ref "U1") (pin "1") (pinfunction "UART0_TX/GP0_1") (pintype "bidirectional"))
      (node (ref "U3") (pin "3") (pinfunction "A_3") (pintype "input"))
    )
    (net (code "23") (name "/PAM8302_EN") (class "Default")
      (node (ref "U1") (pin "34") (pinfunction "ADC2/GP28_34") (pintype "bidirectional"))
      (node (ref "U5") (pin "1") (pinfunction "~{SD}_1") (pintype "input"))
    )
    (net (code "24") (name "/SW1") (class "Default")
      (node (ref "J1") (pin "1") (pinfunction "1_1") (pintype "passive"))
      (node (ref "JP1") (pin "1") (pinfunction "1_1") (pintype "passive"))
      (node (ref "U1") (pin "4") (pinfunction "GP2_4") (pintype "bidirectional"))
    )
    (net (code "25") (name "/SW2") (class "Default")
      (node (ref "J1") (pin "2") (pinfunction "2_2") (pintype "passive"))
      (node (ref "JP2") (pin "1") (pinfunction "1_1") (pintype "passive"))
      (node (ref "U1") (pin "5") (pinfunction "GP3_5") (pintype "bidirectional"))
    )
    (net (code "26") (name "/SW3") (class "Default")
      (node (ref "J1") (pin "3") (pinfunction "3_3") (pintype "passive"))
      (node (ref "JP3") (pin "1") (pinfunction "1_1") (pintype "passive"))
      (node (ref "U1") (pin "6") (pinfunction "GP4_6") (pintype "bidirectional"))
    )
    (net (code "27") (name "/SW4") (class "Default")
      (node (ref "J1") (pin "4") (pinfunction "4_4") (pintype "passive"))
      (node (ref "JP4") (pin "1") (pinfunction "1_1") (pintype "passive"))
      (node (ref "U1") (pin "7") (pinfunction "GP5_7") (pintype "bidirectional"))
    )
    (net (code "28") (name "/SW5") (class "Default")
      (node (ref "J1") (pin "5") (pinfunction "5_5") (pintype "passive"))
      (node (ref "JP5") (pin "1") (pinfunction "1_1") (pintype "passive"))
      (node (ref "U1") (pin "9") (pinfunction "GP6_9") (pintype "bidirectional"))
    )
    (net (code "29") (name "/SW6") (class "Default")
      (node (ref "J1") (pin "6") (pinfunction "6_6") (pintype "passive"))
      (node (ref "JP6") (pin "1") (pinfunction "1_1") (pintype "passive"))
      (node (ref "U1") (pin "10") (pinfunction "GP7_10") (pintype "bidirectional"))
    )
    (net (code "30") (name "/SW7") (class "Default")
      (node (ref "J2") (pin "1") (pinfunction "1_1") (pintype "passive"))
      (node (ref "JP7") (pin "1") (pinfunction "1_1") (pintype "passive"))
      (node (ref "U1") (pin "11") (pinfunction "GP8_11") (pintype "bidirectional"))
    )
    (net (code "31") (name "/SW8") (class "Default")
      (node (ref "J2") (pin "2") (pinfunction "2_2") (pintype "passive"))
      (node (ref "JP8") (pin "1") (pinfunction "1_1") (pintype "passive"))
      (node (ref "U1") (pin "12") (pinfunction "GP9_12") (pintype "bidirectional"))
    )
    (net (code "32") (name "/SW9") (class "Default")
      (node (ref "J2") (pin "3") (pinfunction "3_3") (pintype "passive"))
      (node (ref "JP9") (pin "1") (pinfunction "1_1") (pintype "passive"))
      (node (ref "U1") (pin "14") (pinfunction "GP10_14") (pintype "bidirectional"))
    )
    (net (code "33") (name "/SW10") (class "Default")
      (node (ref "J2") (pin "4") (pinfunction "4_4") (pintype "passive"))
      (node (ref "JP10") (pin "1") (pinfunction "1_1") (pintype "passive"))
      (node (ref "U1") (pin "15") (pinfunction "GP11_15") (pintype "bidirectional"))
    )
    (net (code "34") (name "/SW11") (class "Default")
      (node (ref "J2") (pin "5") (pinfunction "5_5") (pintype "passive"))
      (node (ref "JP11") (pin "1") (pinfunction "1_1") (pintype "passive"))
      (node (ref "U1") (pin "16") (pinfunction "GP12_16") (pintype "bidirectional"))
    )
    (net (code "35") (name "/SW12") (class "Default")
      (node (ref "J2") (pin "6") (pinfunction "6_6") (pintype "passive"))
      (node (ref "JP12") (pin "1") (pinfunction "1_1") (pintype "passive"))
      (node (ref "U1") (pin "17") (pinfunction "GP13_17") (pintype "bidirectional"))
    )
    (net (code "36") (name "/USB_D_N") (class "Default")
      (node (ref "U1") (pin "TP2") (pinfunction "USB_D-_TP2") (pintype "passive"))
    )
    (net (code "37") (name "/USB_D_P") (class "Default")
      (node (ref "U1") (pin "TP3") (pinfunction "USB_D+_TP3") (pintype "passive"))
    )
    (net (code "38") (name "3.3V") (class "Default")
      (node (ref "C3") (pin "2") (pinfunction "2_2") (pintype "passive"))
      (node (ref "C7") (pin "2") (pinfunction "2_2") (pintype "passive"))
      (node (ref "C8") (pin "2") (pinfunction "2_2") (pintype "passive"))
      (node (ref "C9") (pin "2") (pinfunction "2_2") (pintype "passive"))
      (node (ref "J17") (pin "1") (pinfunction "1_1") (pintype "passive"))
      (node (ref "R1") (pin "2") (pinfunction "2_2") (pintype "passive"))
      (node (ref "R10") (pin "2") (pinfunction "2_2") (pintype "passive"))
      (node (ref "R2") (pin "2") (pinfunction "2_2") (pintype "passive"))
      (node (ref "U1") (pin "36") (pinfunction "3V3(OUT)_36") (pintype "passive"))
      (node (ref "U3") (pin "1") (pinfunction "VCCA_1") (pintype "passive"))
      (node (ref "U4") (pin "8") (pinfunction "VCC_8") (pintype "passive"))
    )
    (net (code "39") (name "ADC_VREF") (class "Default")
      (node (ref "U1") (pin "35") (pinfunction "ADC_VREF_35") (pintype "passive"))
    )
    (net (code "40") (name "GND") (class "Default")
      (node (ref "C1") (pin "1") (pinfunction "1_1") (pintype "passive"))
      (node (ref "C11") (pin "1") (pinfunction "1_1") (pintype "passive"))
      (node (ref "C12") (pin "1") (pinfunction "1_1") (pintype "passive"))
      (node (ref "C13") (pin "1") (pinfunction "1_1") (pintype "passive"))
      (node (ref "C15") (pin "1") (pinfunction "1_1") (pintype "passive"))
      (node (ref "C17") (pin "1") (pinfunction "1_1") (pintype "passive"))
      (node (ref "C2") (pin "1") (pinfunction "1_1") (pintype "passive"))
      (node (ref "C21") (pin "1") (pinfunction "1_1") (pintype "passive"))
      (node (ref "C27") (pin "1") (pinfunction "1_1") (pintype "passive"))
      (node (ref "C3") (pin "1") (pinfunction "1_1") (pintype "passive"))
      (node (ref "C30") (pin "2") (pinfunction "2_2") (pintype "passive"))
      (node (ref "C31") (pin "2") (pinfunction "2_2") (pintype "passive"))
      (node (ref "C32") (pin "2") (pinfunction "2_2") (pintype "passive"))
      (node (ref "C4") (pin "1") (pinfunction "1_1") (pintype "passive"))
      (node (ref "C6") (pin "1") (pinfunction "1_1") (pintype "passive"))
      (node (ref "C7") (pin "1") (pinfunction "1_1") (pintype "passive"))
      (node (ref "C8") (pin "1") (pinfunction "1_1") (pintype "passive"))
      (node (ref "C9") (pin "1") (pinfunction "1_1") (pintype "passive"))
      (node (ref "D1") (pin "2") (pinfunction "C_2") (pintype "passive"))
      (node (ref "D2") (pin "2") (pinfunction "C_2") (pintype "passive"))
      (node (ref "D3") (pin "2") (pinfunction "C_2") (pintype "passive"))
      (node (ref "D4") (pin "2") (pinfunction "C_2") (pintype "passive"))
      (node (ref "J10") (pin "2") (pinfunction "2_2") (pintype "passive"))
      (node (ref "J11") (pin "1") (pinfunction "1_1") (pintype "passive"))
      (node (ref "J13") (pin "1") (pinfunction "1_1") (pintype "passive"))
      (node (ref "J16") (pin "1") (pinfunction "1_1") (pintype "passive"))
      (node (ref "J17") (pin "2") (pinfunction "2_2") (pintype "passive"))
      (node (ref "J3") (pin "1") (pinfunction "1_1") (pintype "passive"))
      (node (ref "J4") (pin "1") (pinfunction "1_1") (pintype "passive"))
      (node (ref "J7") (pin "3") (pinfunction "3_3") (pintype "passive"))
      (node (ref "R13") (pin "1") (pinfunction "1_1") (pintype "passive"))
      (node (ref "R16") (pin "1") (pinfunction "BOT_1") (pintype "passive"))
      (node (ref "R26") (pin "1") (pinfunction "BOT_1") (pintype "passive"))
      (node (ref "R30") (pin "2") (pinfunction "2_2") (pintype "passive"))
      (node (ref "R9") (pin "1") (pinfunction "1_1") (pintype "passive"))
      (node (ref "U1") (pin "13") (pinfunction "GND_13") (pintype "passive"))
      (node (ref "U1") (pin "18") (pinfunction "GND_18") (pintype "passive"))
      (node (ref "U1") (pin "23") (pinfunction "GND_23") (pintype "passive"))
      (node (ref "U1") (pin "28") (pinfunction "GND_28") (pintype "passive"))
      (node (ref "U1") (pin "3") (pinfunction "GND_3") (pintype "passive"))
      (node (ref "U1") (pin "33") (pinfunction "AGND_33") (pintype "passive"))
      (node (ref "U1") (pin "38") (pinfunction "GND_38") (pintype "passive"))
      (node (ref "U1") (pin "8") (pinfunction "GND_8") (pintype "passive"))
      (node (ref "U1") (pin "TP1") (pinfunction "(USB)GND_TP1") (pintype "passive"))
      (node (ref "U2") (pin "1") (pinfunction "1_1") (pintype "passive"))
      (node (ref "U2") (pin "C") (pinfunction "C_C") (pintype "passive"))
      (node (ref "U3") (pin "2") (pinfunction "GND_2") (pintype "passive"))
      (node (ref "U4") (pin "5") (pinfunction "GND_5") (pintype "passive"))
      (node (ref "U5") (pin "7") (pinfunction "GND_7") (pintype "passive"))
      (node (ref "U6") (pin "4") (pinfunction "VCC-_4") (pintype "passive"))
      (node (ref "U7") (pin "4") (pinfunction "VCC-_4") (pintype "passive"))
    )
    (net (code "41") (name "Net-(C5-Pad1)") (class "Default")
      (node (ref "C5") (pin "1") (pinfunction "1_1") (pintype "passive"))
      (node (ref "C6") (pin "2") (pinfunction "2_2") (pintype "passive"))
      (node (ref "R8") (pin "2") (pinfunction "2_2") (pintype "passive"))
      (node (ref "R9") (pin "2") (pinfunction "2_2") (pintype "passive"))
    )
    (net (code "42") (name "Net-(C5-Pad2)") (class "Default")
      (node (ref "C5") (pin "2") (pinfunction "2_2") (pintype "passive"))
      (node (ref "J6") (pin "1") (pinfunction "1_1") (pintype "passive"))
    )
    (net (code "43") (name "Net-(C10-Pad1)") (class "Default")
      (node (ref "C10") (pin "1") (pinfunction "1_1") (pintype "passive"))
      (node (ref "C11") (pin "2") (pinfunction "2_2") (pintype "passive"))
      (node (ref "R12") (pin "2") (pinfunction "2_2") (pintype "passive"))
      (node (ref "R13") (pin "2") (pinfunction "2_2") (pintype "passive"))
    )
    (net (code "44") (name "Net-(C10-Pad2)") (class "Default")
      (node (ref "C10") (pin "2") (pinfunction "2_2") (pintype "passive"))
      (node (ref "J6") (pin "2") (pinfunction "2_2") (pintype "passive"))
    )
    (net (code "45") (name "Net-(C14-Pad2)") (class "Default")
      (node (ref "C14") (pin "2") (pinfunction "2_2") (pintype "passive"))
      (node (ref "J7") (pin "1") (pinfunction "1_1") (pintype "passive"))
      (node (ref "JP15") (pin "2") (pinfunction "2_2") (pintype "passive"))
    )
    (net (code "46") (name "Net-(C15-Pad2)") (class "Default")
      (node (ref "C15") (pin "2") (pinfunction "2_2") (pintype "passive"))
      (node (ref "FB1") (pin "2") (pinfunction "2_2") (pintype "passive"))
      (node (ref "J8") (pin "1") (pinfunction "1_1") (pintype "passive"))
    )
    (net (code "47") (name "Net-(C16-Pad2)") (class "Default")
      (node (ref "C16") (pin "2") (pinfunction "2_2") (pintype "passive"))
      (node (ref "J7") (pin "2") (pinfunction "2_2") (pintype "passive"))
      (node (ref "JP16") (pin "2") (pinfunction "2_2") (pintype "passive"))
    )
    (net (code "48") (name "Net-(C17-Pad2)") (class "Default")
      (node (ref "C17") (pin "2") (pinfunction "2_2") (pintype "passive"))
      (node (ref "FB2") (pin "2") (pinfunction "2_2") (pintype "passive"))
      (node (ref "J8") (pin "2") (pinfunction "2_2") (pintype "passive"))
    )
    (net (code "49") (name "Net-(C20-Pad1)") (class "Default")
      (node (ref "C20") (pin "1") (pinfunction "1_1") (pintype "passive"))
      (node (ref "R18") (pin "2") (pinfunction "2_2") (pintype "passive"))
    )
    (net (code "50") (name "Net-(C26-Pad1)") (class "Default")
      (node (ref "C26") (pin "1") (pinfunction "1_1") (pintype "passive"))
      (node (ref "R27") (pin "2") (pinfunction "2_2") (pintype "passive"))
    )
    (net (code "51") (name "Net-(D1-A)") (class "Default")
      (node (ref "D1") (pin "1") (pinfunction "A_1") (pintype "passive"))
      (node (ref "R31") (pin "1") (pinfunction "1_1") (pintype "passive"))
    )
    (net (code "52") (name "Net-(D2-A)") (class "Default")
      (node (ref "D2") (pin "1") (pinfunction "A_1") (pintype "passive"))
      (node (ref "R32") (pin "1") (pinfunction "1_1") (pintype "passive"))
    )
    (net (code "53") (name "Net-(D3-A)") (class "Default")
      (node (ref "D3") (pin "1") (pinfunction "A_1") (pintype "passive"))
      (node (ref "R33") (pin "1") (pinfunction "1_1") (pintype "passive"))
    )
    (net (code "54") (name "Net-(D4-A)") (class "Default")
      (node (ref "D4") (pin "1") (pinfunction "A_1") (pintype "passive"))
      (node (ref "R34") (pin "1") (pinfunction "1_1") (pintype "passive"))
    )
    (net (code "55") (name "Net-(J3-Pad2)") (class "Default")
      (node (ref "J3") (pin "2") (pinfunction "2_2") (pintype "passive"))
      (node (ref "R6") (pin "1") (pinfunction "1_1") (pintype "passive"))
    )
    (net (code "56") (name "Net-(J3-Pad3)") (class "Default")
      (node (ref "J3") (pin "3") (pinfunction "3_3") (pintype "passive"))
      (node (ref "R7") (pin "2") (pinfunction "2_2") (pintype "passive"))
    )
    (net (code "57") (name "Net-(J4-Pad3)") (class "Default")
      (node (ref "J4") (pin "3") (pinfunction "3_3") (pintype "passive"))
      (node (ref "R11") (pin "1") (pinfunction "1_1") (pintype "passive"))
    )
    (net (code "58") (name "Net-(J5-Pad1)") (class "Default")
      (node (ref "J5") (pin "1") (pinfunction "1_1") (pintype "passive"))
      (node (ref "JP13") (pin "2") (pinfunction "2_2") (pintype "passive"))
      (node (ref "R8") (pin "1") (pinfunction "1_1") (pintype "passive"))
    )
    (net (code "59") (name "Net-(J5-Pad2)") (class "Default")
      (node (ref "J5") (pin "2") (pinfunction "2_2") (pintype "passive"))
      (node (ref "JP14") (pin "2") (pinfunction "2_2") (pintype "passive"))
      (node (ref "R12") (pin "1") (pinfunction "1_1") (pintype "passive"))
    )
    (net (code "60") (name "Net-(J11-Pad3)") (class "Default")
      (node (ref "J11") (pin "3") (pinfunction "3_3") (pintype "passive"))
      (node (ref "J15") (pin "1") (pinfunction "1_1") (pintype "passive"))
      (node (ref "JP18") (pin "2") (pinfunction "2_2") (pintype "passive"))
    )
    (net (code "61") (name "Net-(J12-Pad1)") (class "Default")
      (node (ref "J12") (pin "1") (pinfunction "1_1") (pintype "passive"))
      (node (ref "JP17") (pin "2") (pinfunction "2_2") (pintype "passive"))
      (node (ref "R15") (pin "1") (pinfunction "1_1") (pintype "passive"))
    )
    (net (code "62") (name "Net-(J12-Pad2)") (class "Default")
      (node (ref "J12") (pin "2") (pinfunction "2_2") (pintype "passive"))
      (node (ref "JP21") (pin "2") (pinfunction "2_2") (pintype "passive"))
      (node (ref "R24") (pin "1") (pinfunction "1_1") (pintype "passive"))
    )
    (net (code "63") (name "Net-(J13-Pad3)") (class "Default")
      (node (ref "J13") (pin "3") (pinfunction "3_3") (pintype "passive"))
      (node (ref "J15") (pin "2") (pinfunction "2_2") (pintype "passive"))
      (node (ref "JP22") (pin "2") (pinfunction "2_2") (pintype "passive"))
    )
    (net (code "64") (name "Net-(J15-Pad3)") (class "Default")
      (node (ref "J15") (pin "3") (pinfunction "3_3") (pintype "passive"))
      (node (ref "J16") (pin "3") (pinfunction "3_3") (pintype "passive"))
      (node (ref "JP23") (pin "2") (pinfunction "2_2") (pintype "passive"))
    )
    (net (code "65") (name "Net-(JP1-Pad2)") (class "Default")
      (node (ref "JP1") (pin "2") (pinfunction "2_2") (pintype "passive"))
      (node (ref "SW1") (pin "1") (pinfunction "1_1") (pintype "passive"))
    )
    (net (code "66") (name "Net-(JP2-Pad2)") (class "Default")
      (node (ref "JP2") (pin "2") (pinfunction "2_2") (pintype "passive"))
      (node (ref "SW2") (pin "1") (pinfunction "1_1") (pintype "passive"))
    )
    (net (code "67") (name "Net-(JP3-Pad2)") (class "Default")
      (node (ref "JP3") (pin "2") (pinfunction "2_2") (pintype "passive"))
      (node (ref "SW3") (pin "1") (pinfunction "1_1") (pintype "passive"))
    )
    (net (code "68") (name "Net-(JP4-Pad2)") (class "Default")
      (node (ref "JP4") (pin "2") (pinfunction "2_2") (pintype "passive"))
      (node (ref "SW4") (pin "1") (pinfunction "1_1") (pintype "passive"))
    )
    (net (code "69") (name "Net-(JP5-Pad2)") (class "Default")
      (node (ref "JP5") (pin "2") (pinfunction "2_2") (pintype "passive"))
      (node (ref "SW5") (pin "1") (pinfunction "1_1") (pintype "passive"))
    )
    (net (code "70") (name "Net-(JP6-Pad2)") (class "Default")
      (node (ref "JP6") (pin "2") (pinfunction "2_2") (pintype "passive"))
      (node (ref "SW6") (pin "1") (pinfunction "1_1") (pintype "passive"))
    )
    (net (code "71") (name "Net-(JP7-Pad2)") (class "Default")
      (node (ref "JP7") (pin "2") (pinfunction "2_2") (pintype "passive"))
      (node (ref "SW7") (pin "1") (pinfunction "1_1") (pintype "passive"))
    )
    (net (code "72") (name "Net-(JP8-Pad2)") (class "Default")
      (node (ref "JP8") (pin "2") (pinfunction "2_2") (pintype "passive"))
      (node (ref "SW8") (pin "1") (pinfunction "1_1") (pintype "passive"))
    )
    (net (code "73") (name "Net-(JP9-Pad2)") (class "Default")
      (node (ref "JP9") (pin "2") (pinfunction "2_2") (pintype "passive"))
      (node (ref "SW9") (pin "1") (pinfunction "1_1") (pintype "passive"))
    )
    (net (code "74") (name "Net-(JP10-Pad2)") (class "Default")
      (node (ref "JP10") (pin "2") (pinfunction "2_2") (pintype "passive"))
      (node (ref "SW10") (pin "1") (pinfunction "1_1") (pintype "passive"))
    )
    (net (code "75") (name "Net-(JP11-Pad2)") (class "Default")
      (node (ref "JP11") (pin "2") (pinfunction "2_2") (pintype "passive"))
      (node (ref "SW11") (pin "1") (pinfunction "1_1") (pintype "passive"))
    )
    (net (code "76") (name "Net-(JP12-Pad2)") (class "Default")
      (node (ref "JP12") (pin "2") (pinfunction "2_2") (pintype "passive"))
      (node (ref "SW12") (pin "1") (pinfunction "1_1") (pintype "passive"))
    )
    (net (code "77") (name "Net-(R1-Pad1)") (class "Default")
      (node (ref "R1") (pin "1") (pinfunction "1_1") (pintype "passive"))
      (node (ref "R3") (pin "1") (pinfunction "1_1") (pintype "passive"))
      (node (ref "U2") (pin "A") (pinfunction "A_A") (pintype "passive"))
    )
    (net (code "78") (name "Net-(R2-Pad1)") (class "Default")
      (node (ref "R2") (pin "1") (pinfunction "1_1") (pintype "passive"))
      (node (ref "R4") (pin "1") (pinfunction "1_1") (pintype "passive"))
      (node (ref "U2") (pin "B") (pinfunction "B_B") (pintype "passive"))
    )
    (net (code "79") (name "Net-(R16-TAP)") (class "Default")
      (node (ref "C20") (pin "2") (pinfunction "2_2") (pintype "passive"))
      (node (ref "R16") (pin "2") (pinfunction "TAP_2") (pintype "passive"))
    )
    (net (code "80") (name "Net-(R16-TOP)") (class "Default")
      (node (ref "C21") (pin "2") (pinfunction "2_2") (pintype "passive"))
      (node (ref "R15") (pin "2") (pinfunction "2_2") (pintype "passive"))
      (node (ref "R16") (pin "3") (pinfunction "TOP_3") (pintype "passive"))
    )
    (net (code "81") (name "Net-(R26-TAP)") (class "Default")
      (node (ref "C26") (pin "2") (pinfunction "2_2") (pintype "passive"))
      (node (ref "R26") (pin "2") (pinfunction "TAP_2") (pintype "passive"))
    )
    (net (code "82") (name "Net-(R26-TOP)") (class "Default")
      (node (ref "C27") (pin "2") (pinfunction "2_2") (pintype "passive"))
      (node (ref "R24") (pin "2") (pinfunction "2_2") (pintype "passive"))
      (node (ref "R26") (pin "3") (pinfunction "TOP_3") (pintype "passive"))
    )
    (net (code "83") (name "Net-(U3-B)") (class "Default")
      (node (ref "R7") (pin "1") (pinfunction "1_1") (pintype "passive"))
      (node (ref "U3") (pin "4") (pinfunction "B_4") (pintype "output"))
    )
    (net (code "84") (name "Net-(U3-OE)") (class "Default")
      (node (ref "R5") (pin "1") (pinfunction "1_1") (pintype "passive"))
      (node (ref "U3") (pin "5") (pinfunction "OE_5") (pintype "input"))
    )
    (net (code "85") (name "Net-(U4-A)") (class "Default")
      (node (ref "R11") (pin "2") (pinfunction "2_2") (pintype "passive"))
      (node (ref "U4") (pin "2") (pinfunction "A_2") (pintype "passive"))
    )
    (net (code "86") (name "Net-(U4-K)") (class "Default")
      (node (ref "J4") (pin "2") (pinfunction "2_2") (pintype "passive"))
      (node (ref "U4") (pin "3") (pinfunction "K_3") (pintype "passive"))
    )
    (net (code "87") (name "Net-(U5-IN+)") (class "Default")
      (node (ref "C14") (pin "1") (pinfunction "1_1") (pintype "passive"))
      (node (ref "U5") (pin "3") (pinfunction "IN+_3") (pintype "input"))
    )
    (net (code "88") (name "Net-(U5-IN-)") (class "Default")
      (node (ref "C16") (pin "1") (pinfunction "1_1") (pintype "passive"))
      (node (ref "U5") (pin "4") (pinfunction "IN-_4") (pintype "input"))
    )
    (net (code "89") (name "Net-(U5-VO+)") (class "Default")
      (node (ref "FB1") (pin "1") (pinfunction "1_1") (pintype "passive"))
      (node (ref "U5") (pin "5") (pinfunction "VO+_5") (pintype "output"))
    )
    (net (code "90") (name "Net-(U5-VO-)") (class "Default")
      (node (ref "FB2") (pin "1") (pinfunction "1_1") (pintype "passive"))
      (node (ref "U5") (pin "8") (pinfunction "VO-_8") (pintype "output"))
    )
    (net (code "91") (name "Net-(U6A-IN1-)") (class "Default")
      (node (ref "C18") (pin "2") (pinfunction "2_2") (pintype "passive"))
      (node (ref "R14") (pin "2") (pinfunction "2_2") (pintype "passive"))
      (node (ref "R18") (pin "1") (pinfunction "1_1") (pintype "passive"))
      (node (ref "U6") (pin "2") (pinfunction "IN1-_2") (pintype "passive"))
    )
    (net (code "92") (name "Net-(U6A-OUT1)") (class "Default")
      (node (ref "C18") (pin "1") (pinfunction "1_1") (pintype "passive"))
      (node (ref "C19") (pin "2") (pinfunction "2_2") (pintype "passive"))
      (node (ref "C22") (pin "2") (pinfunction "2_2") (pintype "passive"))
      (node (ref "R14") (pin "1") (pinfunction "1_1") (pintype "passive"))
      (node (ref "U6") (pin "1") (pinfunction "OUT1_1") (pintype "passive"))
    )
    (net (code "93") (name "Net-(U6B-IN2-)") (class "Default")
      (node (ref "C24") (pin "2") (pinfunction "2_2") (pintype "passive"))
      (node (ref "R23") (pin "2") (pinfunction "2_2") (pintype "passive"))
      (node (ref "R27") (pin "1") (pinfunction "1_1") (pintype "passive"))
      (node (ref "U6") (pin "6") (pinfunction "IN2-_6") (pintype "passive"))
    )
    (net (code "94") (name "Net-(U6B-OUT2)") (class "Default")
      (node (ref "C24") (pin "1") (pinfunction "1_1") (pintype "passive"))
      (node (ref "C25") (pin "2") (pinfunction "2_2") (pintype "passive"))
      (node (ref "C28") (pin "2") (pinfunction "2_2") (pintype "passive"))
      (node (ref "R23") (pin "1") (pinfunction "1_1") (pintype "passive"))
      (node (ref "U6") (pin "7") (pinfunction "OUT2_7") (pintype "passive"))
    )
    (net (code "95") (name "Net-(U7A-IN1-)") (class "Default")
      (node (ref "R17") (pin "2") (pinfunction "2_2") (pintype "passive"))
      (node (ref "R19") (pin "1") (pinfunction "1_1") (pintype "passive"))
      (node (ref "R20") (pin "1") (pinfunction "1_1") (pintype "passive"))
      (node (ref "U7") (pin "2") (pinfunction "IN1-_2") (pintype "passive"))
    )
    (net (code "96") (name "Net-(U7B-IN2+)") (class "Default")
      (node (ref "R25") (pin "1") (pinfunction "1_1") (pintype "passive"))
      (node (ref "R28") (pin "1") (pinfunction "1_1") (pintype "passive"))
      (node (ref "U7") (pin "5") (pinfunction "IN2+_5") (pintype "passive"))
    )
    (net (code "97") (name "Net-(U7B-IN2-)") (class "Default")
      (node (ref "R21") (pin "1") (pinfunction "1_1") (pintype "passive"))
      (node (ref "R22") (pin "2") (pinfunction "2_2") (pintype "passive"))
      (node (ref "U7") (pin "6") (pinfunction "IN2-_6") (pintype "passive"))
    )
    (net (code "98") (name "USB_VBUS") (class "Default")
      (node (ref "C12") (pin "2") (pinfunction "2_2") (pintype "passive"))
      (node (ref "C13") (pin "2") (pinfunction "2_2") (pintype "passive"))
      (node (ref "C29") (pin "1") (pinfunction "1_1") (pintype "passive"))
      (node (ref "C31") (pin "1") (pinfunction "1_1") (pintype "passive"))
      (node (ref "C32") (pin "1") (pinfunction "1_1") (pintype "passive"))
      (node (ref "C4") (pin "2") (pinfunction "2_2") (pintype "passive"))
      (node (ref "R29") (pin "1") (pinfunction "1_1") (pintype "passive"))
      (node (ref "R5") (pin "2") (pinfunction "2_2") (pintype "passive"))
      (node (ref "R6") (pin "2") (pinfunction "2_2") (pintype "passive"))
      (node (ref "U1") (pin "40") (pinfunction "VBUS_40") (pintype "passive"))
      (node (ref "U3") (pin "6") (pinfunction "VCCB_6") (pintype "passive"))
      (node (ref "U5") (pin "6") (pinfunction "VDD_6") (pintype "passive"))
      (node (ref "U6") (pin "8") (pinfunction "VCC+_8") (pintype "passive"))
      (node (ref "U7") (pin "8") (pinfunction "VCC+_8") (pintype "passive"))
    )
    (net (code "99") (name "VG") (class "Default")
      (node (ref "C29") (pin "2") (pinfunction "2_2") (pintype "passive"))
      (node (ref "C30") (pin "1") (pinfunction "1_1") (pintype "passive"))
      (node (ref "R21") (pin "2") (pinfunction "2_2") (pintype "passive"))
      (node (ref "R29") (pin "2") (pinfunction "2_2") (pintype "passive"))
      (node (ref "R30") (pin "1") (pinfunction "1_1") (pintype "passive"))
      (node (ref "U6") (pin "3") (pinfunction "IN1+_3") (pintype "passive"))
      (node (ref "U6") (pin "5") (pinfunction "IN2+_5") (pintype "passive"))
      (node (ref "U7") (pin "3") (pinfunction "IN1+_3") (pintype "passive"))
    )
    (net (code "100") (name "unconnected-(J11-Pad2)") (class "Default")
      (node (ref "J11") (pin "2") (pinfunction "2_2") (pintype "passive"))
    )
    (net (code "101") (name "unconnected-(J13-Pad2)") (class "Default")
      (node (ref "J13") (pin "2") (pinfunction "2_2") (pintype "passive"))
    )
    (net (code "102") (name "unconnected-(J16-Pad2)") (class "Default")
      (node (ref "J16") (pin "2") (pinfunction "2_2") (pintype "passive"))
    )
    (net (code "103") (name "unconnected-(U1A-LED{slash}GP25-PadTP5)") (class "Default")
      (node (ref "U1") (pin "TP5") (pinfunction "LED/GP25_TP5") (pintype "bidirectional+no_connect"))
    )
    (net (code "104") (name "unconnected-(U1A-SMPS_PS{slash}GP23-PadTP4)") (class "Default")
      (node (ref "U1") (pin "TP4") (pinfunction "SMPS_PS/GP23_TP4") (pintype "bidirectional+no_connect"))
    )
    (net (code "105") (name "unconnected-(U1B-3V3_EN-Pad37)") (class "Default")
      (node (ref "U1") (pin "37") (pinfunction "3V3_EN_37") (pintype "passive+no_connect"))
    )
    (net (code "106") (name "unconnected-(U1B-BOOTSEL-PadTP6)") (class "Default")
      (node (ref "U1") (pin "TP6") (pinfunction "BOOTSEL_TP6") (pintype "passive"))
    )
    (net (code "107") (name "unconnected-(U1B-RUN-Pad30)") (class "Default")
      (node (ref "U1") (pin "30") (pinfunction "RUN_30") (pintype "passive+no_connect"))
    )
    (net (code "108") (name "unconnected-(U1B-VSYS-Pad39)") (class "Default")
      (node (ref "U1") (pin "39") (pinfunction "VSYS_39") (pintype "passive"))
    )
    (net (code "109") (name "unconnected-(U2A-SHLD-Pad3)") (class "Default")
      (node (ref "U2") (pin "3") (pinfunction "SHLD_3") (pintype "passive"))
    )
    (net (code "110") (name "unconnected-(U2A-SHLD-Pad4)") (class "Default")
      (node (ref "U2") (pin "4") (pinfunction "SHLD_4") (pintype "passive"))
    )
    (net (code "111") (name "unconnected-(U4-NC-Pad1)") (class "Default")
      (node (ref "U4") (pin "1") (pinfunction "NC_1") (pintype "passive+no_connect"))
    )
    (net (code "112") (name "unconnected-(U4-NC-Pad4)") (class "Default")
      (node (ref "U4") (pin "4") (pinfunction "NC_4") (pintype "passive+no_connect"))
    )
    (net (code "113") (name "unconnected-(U4-VB-Pad7)") (class "Default")
      (node (ref "U4") (pin "7") (pinfunction "VB_7") (pintype "passive+no_connect"))
    )
    (net (code "114") (name "unconnected-(U5-NC-Pad2)") (class "Default")
      (node (ref "U5") (pin "2") (pinfunction "NC_2") (pintype "passive+no_connect"))
    )
  )
)
